# opamp-only.net
KiCad netlist of a schematic drawn in EAGLE
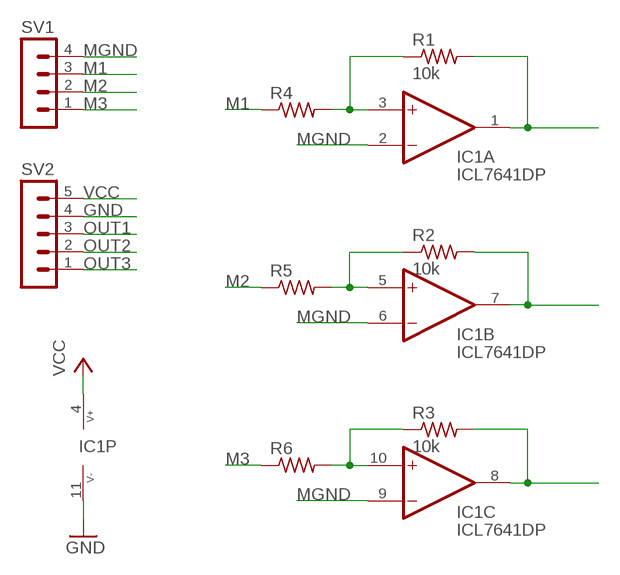
[diagram p0: schematic, sheet 1]

(export (version "E")
  (design (tool "Eeschema 10.0.6"))
  (components
    (comp (ref "IC1")
      (value "ICL7641DP")
      (footprint "eagle-import:DIL14")
      (libsource (lib "eagle-import") (part "ICL764DP1"))
    )
    (comp (ref "R1")
      (value "10k")
      (footprint "eagle-import:0207_7")
      (libsource (lib "eagle-import") (part "R-US_0207/7"))
    )
    (comp (ref "R2")
      (value "10k")
      (footprint "eagle-import:0207_7")
      (libsource (lib "eagle-import") (part "R-US_0207/7"))
    )
    (comp (ref "R3")
      (value "10k")
      (footprint "eagle-import:0207_7")
      (libsource (lib "eagle-import") (part "R-US_0207/7"))
    )
    (comp (ref "R4")
      (value "R-US_0207/7")
      (footprint "eagle-import:0207_7")
      (libsource (lib "eagle-import") (part "R-US_0207/7"))
    )
    (comp (ref "R5")
      (value "R-US_0207/7")
      (footprint "eagle-import:0207_7")
      (libsource (lib "eagle-import") (part "R-US_0207/7"))
    )
    (comp (ref "R6")
      (value "R-US_0207/7")
      (footprint "eagle-import:0207_7")
      (libsource (lib "eagle-import") (part "R-US_0207/7"))
    )
    (comp (ref "SV1")
      (value "MA04-1")
      (footprint "eagle-import:MA04-1")
      (libsource (lib "eagle-import") (part "MA04-1"))
    )
    (comp (ref "SV2")
      (value "MA05-1")
      (footprint "eagle-import:MA05-1")
      (libsource (lib "eagle-import") (part "MA05-1"))
    )
  )
  (nets
    (net (code "1") (name "/M1") (class "Default")
      (node (ref "R4") (pin "1") (pinfunction "1_1") (pintype "passive"))
      (node (ref "SV1") (pin "3") (pinfunction "3_3") (pintype "passive"))
    )
    (net (code "2") (name "/M2") (class "Default")
      (node (ref "R5") (pin "1") (pinfunction "1_1") (pintype "passive"))
      (node (ref "SV1") (pin "2") (pinfunction "2_2") (pintype "passive"))
    )
    (net (code "3") (name "/M3") (class "Default")
      (node (ref "R6") (pin "1") (pinfunction "1_1") (pintype "passive"))
      (node (ref "SV1") (pin "1") (pinfunction "1_1") (pintype "passive"))
    )
    (net (code "4") (name "/MGND") (class "Default")
      (node (ref "IC1") (pin "2") (pinfunction "-IN_2") (pintype "input"))
      (node (ref "IC1") (pin "6") (pinfunction "-IN_6") (pintype "input"))
      (node (ref "IC1") (pin "9") (pinfunction "-IN_9") (pintype "input"))
      (node (ref "SV1") (pin "4") (pinfunction "4_4") (pintype "passive"))
    )
    (net (code "5") (name "/OUT1") (class "Default")
      (node (ref "IC1") (pin "1") (pinfunction "OUT_1") (pintype "output"))
      (node (ref "R1") (pin "2") (pinfunction "2_2") (pintype "passive"))
      (node (ref "SV2") (pin "3") (pinfunction "3_3") (pintype "passive"))
    )
    (net (code "6") (name "/OUT2") (class "Default")
      (node (ref "IC1") (pin "7") (pinfunction "OUT_7") (pintype "output"))
      (node (ref "R2") (pin "2") (pinfunction "2_2") (pintype "passive"))
      (node (ref "SV2") (pin "2") (pinfunction "2_2") (pintype "passive"))
    )
    (net (code "7") (name "/OUT3") (class "Default")
      (node (ref "IC1") (pin "8") (pinfunction "OUT_8") (pintype "output"))
      (node (ref "R3") (pin "2") (pinfunction "2_2") (pintype "passive"))
      (node (ref "SV2") (pin "1") (pinfunction "1_1") (pintype "passive"))
    )
    (net (code "8") (name "GND") (class "Default")
      (node (ref "IC1") (pin "11") (pinfunction "V-_11") (pintype "power_in"))
      (node (ref "SV2") (pin "4") (pinfunction "4_4") (pintype "passive"))
    )
    (net (code "9") (name "Net-(IC1A-+IN)") (class "Default")
      (node (ref "IC1") (pin "3") (pinfunction "+IN_3") (pintype "input"))
      (node (ref "R1") (pin "1") (pinfunction "1_1") (pintype "passive"))
      (node (ref "R4") (pin "2") (pinfunction "2_2") (pintype "passive"))
    )
    (net (code "10") (name "Net-(IC1B-+IN)") (class "Default")
      (node (ref "IC1") (pin "5") (pinfunction "+IN_5") (pintype "input"))
      (node (ref "R2") (pin "1") (pinfunction "1_1") (pintype "passive"))
      (node (ref "R5") (pin "2") (pinfunction "2_2") (pintype "passive"))
    )
    (net (code "11") (name "Net-(IC1C-+IN)") (class "Default")
      (node (ref "IC1") (pin "10") (pinfunction "+IN_10") (pintype "input"))
      (node (ref "R3") (pin "1") (pinfunction "1_1") (pintype "passive"))
      (node (ref "R6") (pin "2") (pinfunction "2_2") (pintype "passive"))
    )
    (net (code "12") (name "VCC") (class "Default")
      (node (ref "IC1") (pin "4") (pinfunction "V+_4") (pintype "power_in"))
      (node (ref "SV2") (pin "5") (pinfunction "5_5") (pintype "passive"))
    )
  )
)
